# UI.net
KiCad netlist of a schematic drawn in Altium Designer
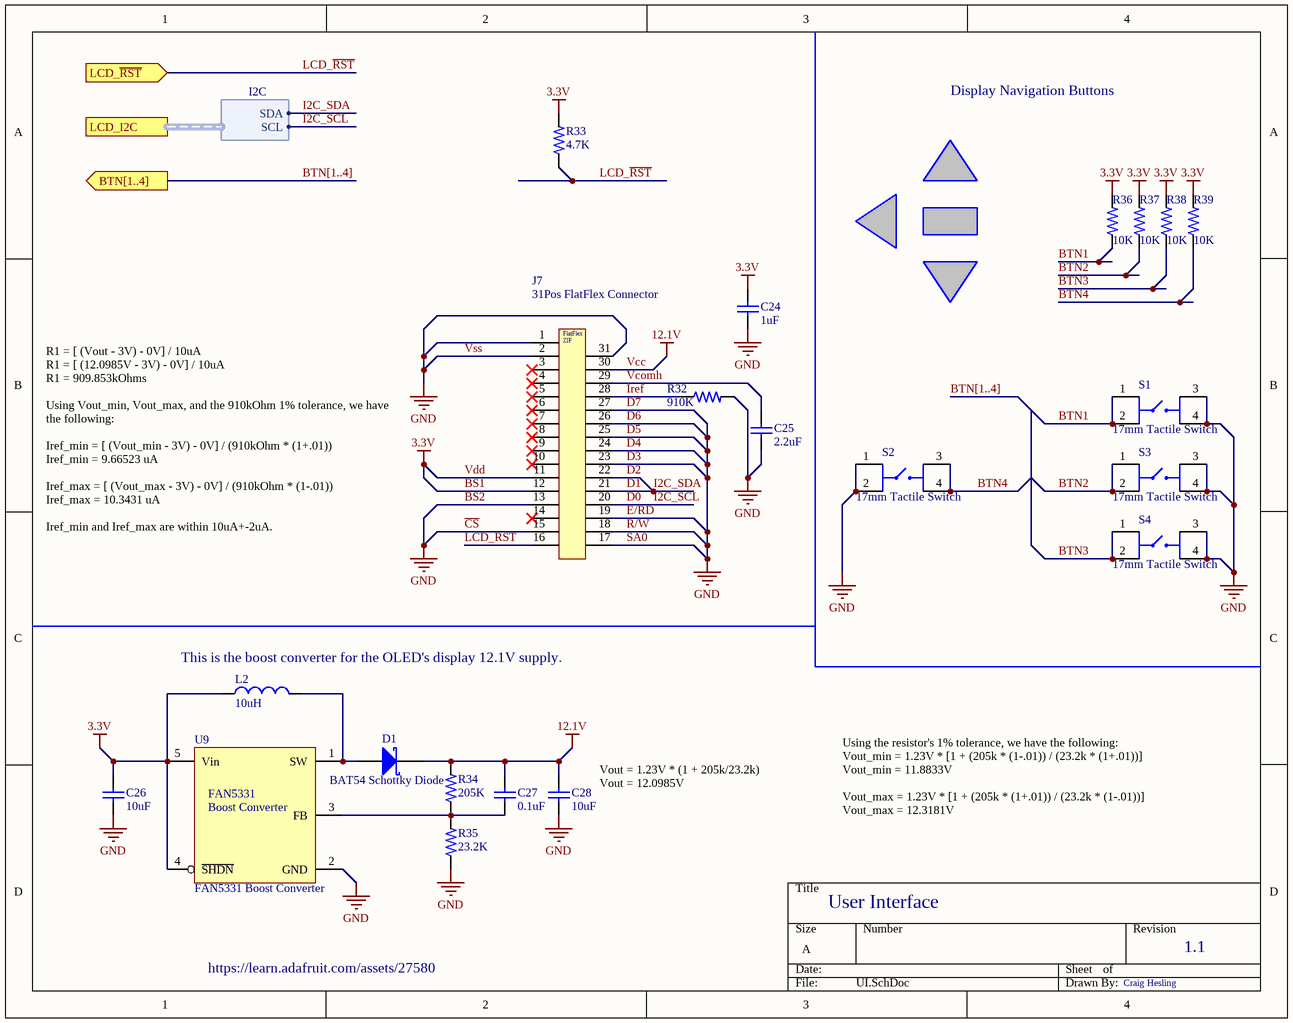
[diagram p0: UI.SchDoc]

(export (version "E")
  (design (tool "Eeschema 10.0.6"))
  (components
    (comp (ref "C24")
      (value "1uF")
      (footprint "CAPC1608X09L - CAP0603")
      (description "SMT 0603 Ceramic Capacitor")
      (fields (field (name "TOLERANCE") "5%") (field (name "VOLTAGE") "10V"))
      (libsource (lib "Passives") (part "CAP0603 1uF 5% 10V X7R"))
    )
    (comp (ref "C25")
      (value "2.2uF")
      (footprint "CAPC1608X09L - CAP0603")
      (description "SMT 0603 Ceramic Capacitor")
      (fields (field (name "TOLERANCE") "10%") (field (name "VOLTAGE") "6.3V"))
      (libsource (lib "Passives") (part "CAP0603 2.2uF 10% 6.3V X7R"))
    )
    (comp (ref "C26")
      (value "10uF")
      (footprint "CAPC2013X14L - CAP0805 1.45mm Tall")
      (description "SMT 0805 Ceramic Capacitor")
      (fields (field (name "TOLERANCE") "10%") (field (name "VOLTAGE") "6.3V"))
      (libsource (lib "Passives") (part "CAP0805 10uF 10% 6.3V X5R"))
    )
    (comp (ref "C27")
      (value "0.1uF")
      (footprint "CAPC1608X09L - CAP0603")
      (description "SMT 0603 Ceramic Capacitor")
      (fields (field (name "TOLERANCE") "10%") (field (name "VOLTAGE") "25V"))
      (libsource (lib "Passives") (part "CAP0603 0.1uF 10% 25V X7R"))
    )
    (comp (ref "C28")
      (value "10uF")
      (footprint "CAPC3216X18L - CAP1206 1.8MM TALL")
      (description "SMT 1206 Ceramic Capacitor")
      (fields (field (name "TOLERANCE") "10%") (field (name "VOLTAGE") "16V"))
      (libsource (lib "Passives") (part "CAP1206 10uF 10% 16V X5R"))
    )
    (comp (ref "D1")
      (value "BAT54 Schottky Diode")
      (footprint "SOT95P240X120-3L - ON Semi")
      (description "ON Semi BAT54 800mV Schottky Diode")
      (libsource (lib "Actives") (part "BAT54"))
    )
    (comp (ref "J7")
      (value "31Pos FlatFlex Connector")
      (footprint "31 Position Flat Flex ZIF Connector")
      (description "TE 3-1734839-1 31 Position Flat Flex ZIF Connector")
      (libsource (lib "Connectors") (part "31 Position Flat Flex ZIF Connector"))
    )
    (comp (ref "L2")
      (value "10uH")
      (footprint "INDP4949X20L")
      (description "SMT Wire Wound Inductor")
      (fields (field (name "TOLERANCE") "20%"))
      (libsource (lib "Passives") (part "INDWW 10uH 1.45A 20% 144mOhm 24MHz"))
    )
    (comp (ref "R32")
      (value "910K")
      (footprint "RESC1608X06L - RES0603")
      (description "SMT 0603 Ceramic Resistor")
      (fields (field (name "POWER") "1/10W") (field (name "TOLERANCE") "1%"))
      (libsource (lib "Passives") (part "RES0603 910K 1% 1/10W"))
    )
    (comp (ref "R33")
      (value "4.7K")
      (footprint "RESC1608X06L - RES0603")
      (description "SMT 0603 Ceramic Resistor")
      (fields (field (name "POWER") "1/10W") (field (name "TOLERANCE") "1%"))
      (libsource (lib "Passives") (part "RES0603 4.7K 1% 1/10W"))
    )
    (comp (ref "R34")
      (value "205K")
      (footprint "RESC1608X06L - RES0603")
      (description "SMT 0603 Ceramic Resistor")
      (fields (field (name "POWER") "1/10W") (field (name "TOLERANCE") "1%"))
      (libsource (lib "Passives") (part "RES0603 205K 1% 1/10W"))
    )
    (comp (ref "R35")
      (value "23.2K")
      (footprint "RESC1608X06L - RES0603")
      (description "SMT 0603 Ceramic Resistor")
      (fields (field (name "POWER") "1/10W") (field (name "TOLERANCE") "1%"))
      (libsource (lib "Passives") (part "RES0603 23.2K 1% 1/10W"))
    )
    (comp (ref "R36")
      (value "10K")
      (footprint "RESC1608X06L - RES0603")
      (description "SMT 0603 Ceramic Resistor")
      (fields (field (name "POWER") "1/10W") (field (name "TOLERANCE") "1%"))
      (libsource (lib "Passives") (part "RES0603 10K 1% 1/10W"))
    )
    (comp (ref "R37")
      (value "10K")
      (footprint "RESC1608X06L - RES0603")
      (description "SMT 0603 Ceramic Resistor")
      (fields (field (name "POWER") "1/10W") (field (name "TOLERANCE") "1%"))
      (libsource (lib "Passives") (part "RES0603 10K 1% 1/10W"))
    )
    (comp (ref "R38")
      (value "10K")
      (footprint "RESC1608X06L - RES0603")
      (description "SMT 0603 Ceramic Resistor")
      (fields (field (name "POWER") "1/10W") (field (name "TOLERANCE") "1%"))
      (libsource (lib "Passives") (part "RES0603 10K 1% 1/10W"))
    )
    (comp (ref "R39")
      (value "10K")
      (footprint "RESC1608X06L - RES0603")
      (description "SMT 0603 Ceramic Resistor")
      (fields (field (name "POWER") "1/10W") (field (name "TOLERANCE") "1%"))
      (libsource (lib "Passives") (part "RES0603 10K 1% 1/10W"))
    )
    (comp (ref "S1")
      (value "17mm Tactile Switch")
      (footprint "TactileSwitchTE17mm")
      (description "TE 3-1825910-1 17mm Tactile Switch")
      (libsource (lib "Misc") (part "TE 3-1825910-1 17mm Tactile Switch"))
    )
    (comp (ref "S2")
      (value "17mm Tactile Switch")
      (footprint "TactileSwitchTE17mm")
      (description "TE 3-1825910-1 17mm Tactile Switch")
      (libsource (lib "Misc") (part "TE 3-1825910-1 17mm Tactile Switch"))
    )
    (comp (ref "S3")
      (value "17mm Tactile Switch")
      (footprint "TactileSwitchTE17mm")
      (description "TE 3-1825910-1 17mm Tactile Switch")
      (libsource (lib "Misc") (part "TE 3-1825910-1 17mm Tactile Switch"))
    )
    (comp (ref "S4")
      (value "17mm Tactile Switch")
      (footprint "TactileSwitchTE17mm")
      (description "TE 3-1825910-1 17mm Tactile Switch")
      (libsource (lib "Misc") (part "TE 3-1825910-1 17mm Tactile Switch"))
    )
    (comp (ref "U9")
      (value "FAN5331 Boost Converter")
      (footprint "SOT95P280X145-5L - ON Semi")
      (description "ON Semi FAN5531 Boost Converter")
      (libsource (lib "Actives") (part "FAN5331"))
    )
  )
  (nets
    (net (code "2") (name "/BTN1") (class "Default")
      (node (ref "R36") (pin "1") (pinfunction "1_1") (pintype "passive"))
      (node (ref "S1") (pin "1") (pinfunction "1_1") (pintype "passive"))
      (node (ref "S1") (pin "2") (pinfunction "2_2") (pintype "passive"))
    )
    (net (code "3") (name "/BTN2") (class "Default")
      (node (ref "R37") (pin "1") (pinfunction "1_1") (pintype "passive"))
      (node (ref "S3") (pin "1") (pinfunction "1_1") (pintype "passive"))
      (node (ref "S3") (pin "2") (pinfunction "2_2") (pintype "passive"))
    )
    (net (code "4") (name "/BTN3") (class "Default")
      (node (ref "R38") (pin "1") (pinfunction "1_1") (pintype "passive"))
      (node (ref "S4") (pin "1") (pinfunction "1_1") (pintype "passive"))
      (node (ref "S4") (pin "2") (pinfunction "2_2") (pintype "passive"))
    )
    (net (code "5") (name "/BTN4") (class "Default")
      (node (ref "R39") (pin "1") (pinfunction "1_1") (pintype "passive"))
      (node (ref "S2") (pin "3") (pinfunction "3_3") (pintype "passive"))
      (node (ref "S2") (pin "4") (pinfunction "4_4") (pintype "passive"))
    )
    (net (code "7") (name "/D0") (class "Default") (node (ref "J7") (pin "20") (pintype "passive")))
    (net (code "8") (name "/D1") (class "Default")
      (node (ref "J7") (pin "21") (pintype "passive"))
      (node (ref "J7") (pin "22") (pintype "passive"))
    )
    (net (code "9") (name "/Iref") (class "Default")
      (node (ref "J7") (pin "28") (pintype "passive"))
      (node (ref "R32") (pin "1") (pinfunction "1_1") (pintype "passive"))
    )
    (net (code "10") (name "/LCD_~{RST}") (class "Default")
      (node (ref "J7") (pin "16") (pintype "passive"))
      (node (ref "R33") (pin "1") (pinfunction "1_1") (pintype "passive"))
    )
    (net (code "11") (name "/Vcomh") (class "Default")
      (node (ref "C25") (pin "2") (pinfunction "2_2") (pintype "passive"))
      (node (ref "J7") (pin "29") (pintype "passive"))
    )
    (net (code "13") (name "3.3V") (class "Default")
      (node (ref "C24") (pin "2") (pinfunction "2_2") (pintype "passive"))
      (node (ref "C26") (pin "2") (pinfunction "2_2") (pintype "passive"))
      (node (ref "J7") (pin "11") (pintype "passive"))
      (node (ref "J7") (pin "12") (pintype "passive"))
      (node (ref "L2") (pin "1") (pinfunction "1_1") (pintype "passive"))
      (node (ref "R33") (pin "2") (pinfunction "2_2") (pintype "passive"))
      (node (ref "R36") (pin "2") (pinfunction "2_2") (pintype "passive"))
      (node (ref "R37") (pin "2") (pinfunction "2_2") (pintype "passive"))
      (node (ref "R38") (pin "2") (pinfunction "2_2") (pintype "passive"))
      (node (ref "R39") (pin "2") (pinfunction "2_2") (pintype "passive"))
      (node (ref "U9") (pin "4") (pinfunction "~{SHDN}_4") (pintype "passive"))
      (node (ref "U9") (pin "5") (pinfunction "Vin_5") (pintype "passive"))
    )
    (net (code "14") (name "12.1V") (class "Default")
      (node (ref "C27") (pin "2") (pinfunction "2_2") (pintype "passive"))
      (node (ref "C28") (pin "2") (pinfunction "2_2") (pintype "passive"))
      (node (ref "D1") (pin "3") (pinfunction "K_3") (pintype "passive"))
      (node (ref "J7") (pin "30") (pintype "passive"))
      (node (ref "R34") (pin "2") (pinfunction "2_2") (pintype "passive"))
    )
    (net (code "15") (name "GND") (class "Default")
      (node (ref "C24") (pin "1") (pinfunction "1_1") (pintype "passive"))
      (node (ref "C25") (pin "1") (pinfunction "1_1") (pintype "passive"))
      (node (ref "C26") (pin "1") (pinfunction "1_1") (pintype "passive"))
      (node (ref "C28") (pin "1") (pinfunction "1_1") (pintype "passive"))
      (node (ref "J7") (pin "1") (pintype "passive"))
      (node (ref "J7") (pin "13") (pintype "passive"))
      (node (ref "J7") (pin "15") (pintype "passive"))
      (node (ref "J7") (pin "17") (pintype "passive"))
      (node (ref "J7") (pin "18") (pintype "passive"))
      (node (ref "J7") (pin "19") (pintype "passive"))
      (node (ref "J7") (pin "2") (pintype "passive"))
      (node (ref "J7") (pin "23") (pintype "passive"))
      (node (ref "J7") (pin "24") (pintype "passive"))
      (node (ref "J7") (pin "25") (pintype "passive"))
      (node (ref "J7") (pin "26") (pintype "passive"))
      (node (ref "J7") (pin "27") (pintype "passive"))
      (node (ref "J7") (pin "31") (pintype "passive"))
      (node (ref "R32") (pin "2") (pinfunction "2_2") (pintype "passive"))
      (node (ref "R35") (pin "1") (pinfunction "1_1") (pintype "passive"))
      (node (ref "S1") (pin "3") (pinfunction "3_3") (pintype "passive"))
      (node (ref "S1") (pin "4") (pinfunction "4_4") (pintype "passive"))
      (node (ref "S2") (pin "1") (pinfunction "1_1") (pintype "passive"))
      (node (ref "S2") (pin "2") (pinfunction "2_2") (pintype "passive"))
      (node (ref "S3") (pin "3") (pinfunction "3_3") (pintype "passive"))
      (node (ref "S3") (pin "4") (pinfunction "4_4") (pintype "passive"))
      (node (ref "S4") (pin "3") (pinfunction "3_3") (pintype "passive"))
      (node (ref "S4") (pin "4") (pinfunction "4_4") (pintype "passive"))
      (node (ref "U9") (pin "2") (pinfunction "GND_2") (pintype "passive"))
    )
    (net (code "16") (name "Net-(D1-A)") (class "Default")
      (node (ref "D1") (pin "1") (pinfunction "A_1") (pintype "passive"))
      (node (ref "L2") (pin "2") (pinfunction "2_2") (pintype "passive"))
      (node (ref "U9") (pin "1") (pinfunction "SW_1") (pintype "passive"))
    )
    (net (code "17") (name "Net-(U9-FB)") (class "Default")
      (node (ref "C27") (pin "1") (pinfunction "1_1") (pintype "passive"))
      (node (ref "R34") (pin "1") (pinfunction "1_1") (pintype "passive"))
      (node (ref "R35") (pin "2") (pinfunction "2_2") (pintype "passive"))
      (node (ref "U9") (pin "3") (pinfunction "FB_3") (pintype "passive"))
    )
    (net (code "18") (name "unconnected-(J7-Pad3)") (class "Default")
      (node (ref "J7") (pin "3") (pintype "passive+no_connect"))
    )
    (net (code "19") (name "unconnected-(J7-Pad4)") (class "Default")
      (node (ref "J7") (pin "4") (pintype "passive+no_connect"))
    )
    (net (code "20") (name "unconnected-(J7-Pad5)") (class "Default")
      (node (ref "J7") (pin "5") (pintype "passive+no_connect"))
    )
    (net (code "21") (name "unconnected-(J7-Pad6)") (class "Default")
      (node (ref "J7") (pin "6") (pintype "passive+no_connect"))
    )
    (net (code "22") (name "unconnected-(J7-Pad7)") (class "Default")
      (node (ref "J7") (pin "7") (pintype "passive+no_connect"))
    )
    (net (code "23") (name "unconnected-(J7-Pad8)") (class "Default")
      (node (ref "J7") (pin "8") (pintype "passive+no_connect"))
    )
    (net (code "24") (name "unconnected-(J7-Pad9)") (class "Default")
      (node (ref "J7") (pin "9") (pintype "passive+no_connect"))
    )
    (net (code "25") (name "unconnected-(J7-Pad10)") (class "Default")
      (node (ref "J7") (pin "10") (pintype "passive+no_connect"))
    )
    (net (code "26") (name "unconnected-(J7-Pad14)") (class "Default")
      (node (ref "J7") (pin "14") (pintype "passive+no_connect"))
    )
  )
)
